# USB_UART_Bridge.net
KiCad netlist of a schematic drawn in Altium Designer
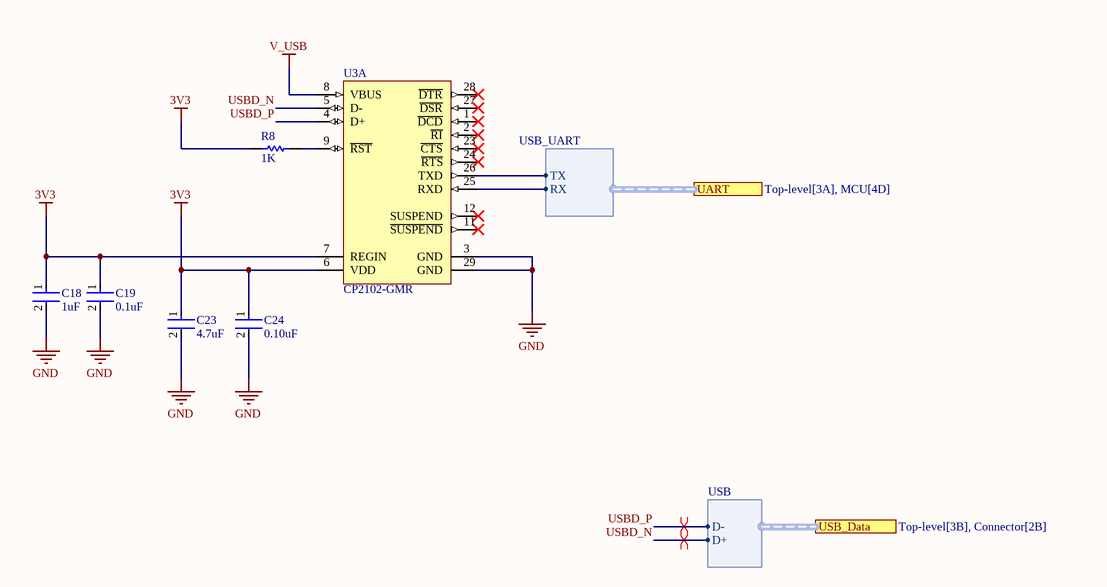
[diagram p0: USB_UART_Bridge.SchDoc]

(export (version "E")
  (design (tool "Eeschema 10.0.6"))
  (components
    (comp (ref "C18")
      (value "1uF")
      (footprint "FP-GRM033-0_09-IPC_A")
      (description "Chip Multilayer Ceramic Capacitors for General Purpose, 0201, 1.0uF, X5R, 15%, 20%, 10V")
      (fields (field (name "TOLERANCE") "20%"))
      (libsource (lib "Altium Content Vault") (part "02cd4be3c70576c341d710602a673aa"))
    )
    (comp (ref "C19")
      (value "0.1uF")
      (footprint "FP-GRM033-0_03-MFG")
      (description "Chip Multilayer Ceramic Capacitors for General Purpose, 0201, 0.10uF, X7S, 22%, 10%, 16V")
      (fields (field (name "TOLERANCE") "10%"))
      (libsource (lib "Altium Content Vault") (part "b4654b650e69147ec39a6b967a45e02"))
    )
    (comp (ref "C23")
      (value "4.7uF")
      (footprint "FP-CC0402-MFG")
      (description "CAP CER 4.7UF 16V X5R 0402")
      (fields
        (field (name "OCTOPART") "https://octopart.com/cc0402mrx5r7bb475-yageo-81932628")
        (field (name "MANUFACTURER PART NUMBER") "CC0402MRX5R7BB475")
      )
      (libsource (lib "Altium Content Vault") (part "11868f565c42a9108669ba33697ecf6"))
    )
    (comp (ref "C24")
      (value "0.10uF")
      (footprint "FP-GRM033-0_03-MFG")
      (description "Chip Multilayer Ceramic Capacitors for General Purpose, 0201, 0.10uF, X7S, 22%, 10%, 16V")
      (fields (field (name "TOLERANCE") "10%"))
      (libsource (lib "Altium Content Vault") (part "b4654b650e69147ec39a6b967a45e02"))
    )
    (comp (ref "R8")
      (value "1K")
      (footprint "RESC0603X28X15ML05T05")
      (fields (field (name "MANUFACTURER") "Vishay Dale") (field (name "PART NUMBER") "CRCW02011K00FNED"))
      (libsource (lib "Altium Content Vault") (part "RES"))
    )
    (comp (ref "U3")
      (value "CP2102-GMR")
      (footprint "SLAB-QFN-28-3125x3125TP_M")
      (description "Single-Chip USB to URAT Bridge, 3.3 V, -40 to 85 degC, 28-Pin QFN, RoHS, Tape and Reel")
      (fields (field (name "MANUFACTURER") "Silicon Labs"))
      (libsource (lib "Altium Content Vault") (part "SLAB-CP210X-QFN-28-29"))
    )
  )
  (nets
    (net (code "3") (name "/RX") (class "Default")
      (node (ref "U3") (pin "25") (pinfunction "RXD_25") (pintype "input"))
    )
    (net (code "4") (name "/TX") (class "Default")
      (node (ref "U3") (pin "26") (pinfunction "TXD_26") (pintype "output"))
    )
    (net (code "5") (name "/USBD_N") (class "Default")
      (node (ref "U3") (pin "5") (pinfunction "D-_5") (pintype "bidirectional"))
    )
    (net (code "6") (name "/USBD_P") (class "Default")
      (node (ref "U3") (pin "4") (pinfunction "D+_4") (pintype "bidirectional"))
    )
    (net (code "9") (name "3V3") (class "Default")
      (node (ref "C18") (pin "1") (pinfunction "1_1") (pintype "passive"))
      (node (ref "C19") (pin "1") (pinfunction "1_1") (pintype "passive"))
      (node (ref "C23") (pin "1") (pinfunction "1_1") (pintype "passive"))
      (node (ref "C24") (pin "1") (pinfunction "1_1") (pintype "passive"))
      (node (ref "R8") (pin "1") (pinfunction "1_1") (pintype "passive"))
      (node (ref "U3") (pin "6") (pinfunction "VDD_6") (pintype "power_in"))
      (node (ref "U3") (pin "7") (pinfunction "REGIN_7") (pintype "power_in"))
    )
    (net (code "10") (name "GND") (class "Default")
      (node (ref "C18") (pin "2") (pinfunction "2_2") (pintype "passive"))
      (node (ref "C19") (pin "2") (pinfunction "2_2") (pintype "passive"))
      (node (ref "C23") (pin "2") (pinfunction "2_2") (pintype "passive"))
      (node (ref "C24") (pin "2") (pinfunction "2_2") (pintype "passive"))
      (node (ref "U3") (pin "29") (pinfunction "GND_29") (pintype "power_in"))
      (node (ref "U3") (pin "3") (pinfunction "GND_3") (pintype "power_in"))
    )
    (net (code "11") (name "Net-(U3A-~{RST})") (class "Default")
      (node (ref "R8") (pin "2") (pinfunction "2_2") (pintype "passive"))
      (node (ref "U3") (pin "9") (pinfunction "~{RST}_9") (pintype "bidirectional"))
    )
    (net (code "12") (name "V_USB") (class "Default")
      (node (ref "U3") (pin "8") (pinfunction "VBUS_8") (pintype "input"))
    )
    (net (code "13") (name "unconnected-(U3A-SUSPEND-Pad12)") (class "Default")
      (node (ref "U3") (pin "12") (pinfunction "SUSPEND_12") (pintype "output+no_connect"))
    )
    (net (code "14") (name "unconnected-(U3A-~{CTS}-Pad23)") (class "Default")
      (node (ref "U3") (pin "23") (pinfunction "~{CTS}_23") (pintype "input+no_connect"))
    )
    (net (code "15") (name "unconnected-(U3A-~{DCD}-Pad1)") (class "Default")
      (node (ref "U3") (pin "1") (pinfunction "~{DCD}_1") (pintype "input+no_connect"))
    )
    (net (code "16") (name "unconnected-(U3A-~{DSR}-Pad27)") (class "Default")
      (node (ref "U3") (pin "27") (pinfunction "~{DSR}_27") (pintype "input+no_connect"))
    )
    (net (code "17") (name "unconnected-(U3A-~{DTR}-Pad28)") (class "Default")
      (node (ref "U3") (pin "28") (pinfunction "~{DTR}_28") (pintype "output+no_connect"))
    )
    (net (code "18") (name "unconnected-(U3A-~{RI}-Pad2)") (class "Default")
      (node (ref "U3") (pin "2") (pinfunction "~{RI}_2") (pintype "input+no_connect"))
    )
    (net (code "19") (name "unconnected-(U3A-~{RTS}-Pad24)") (class "Default")
      (node (ref "U3") (pin "24") (pinfunction "~{RTS}_24") (pintype "output+no_connect"))
    )
    (net (code "20") (name "unconnected-(U3A-~{SUSPEND}-Pad11)") (class "Default")
      (node (ref "U3") (pin "11") (pinfunction "~{SUSPEND}_11") (pintype "output+no_connect"))
    )
  )
)
